# STM3205P_PowerSupply.net
KiCad netlist of a schematic drawn in Altium Designer
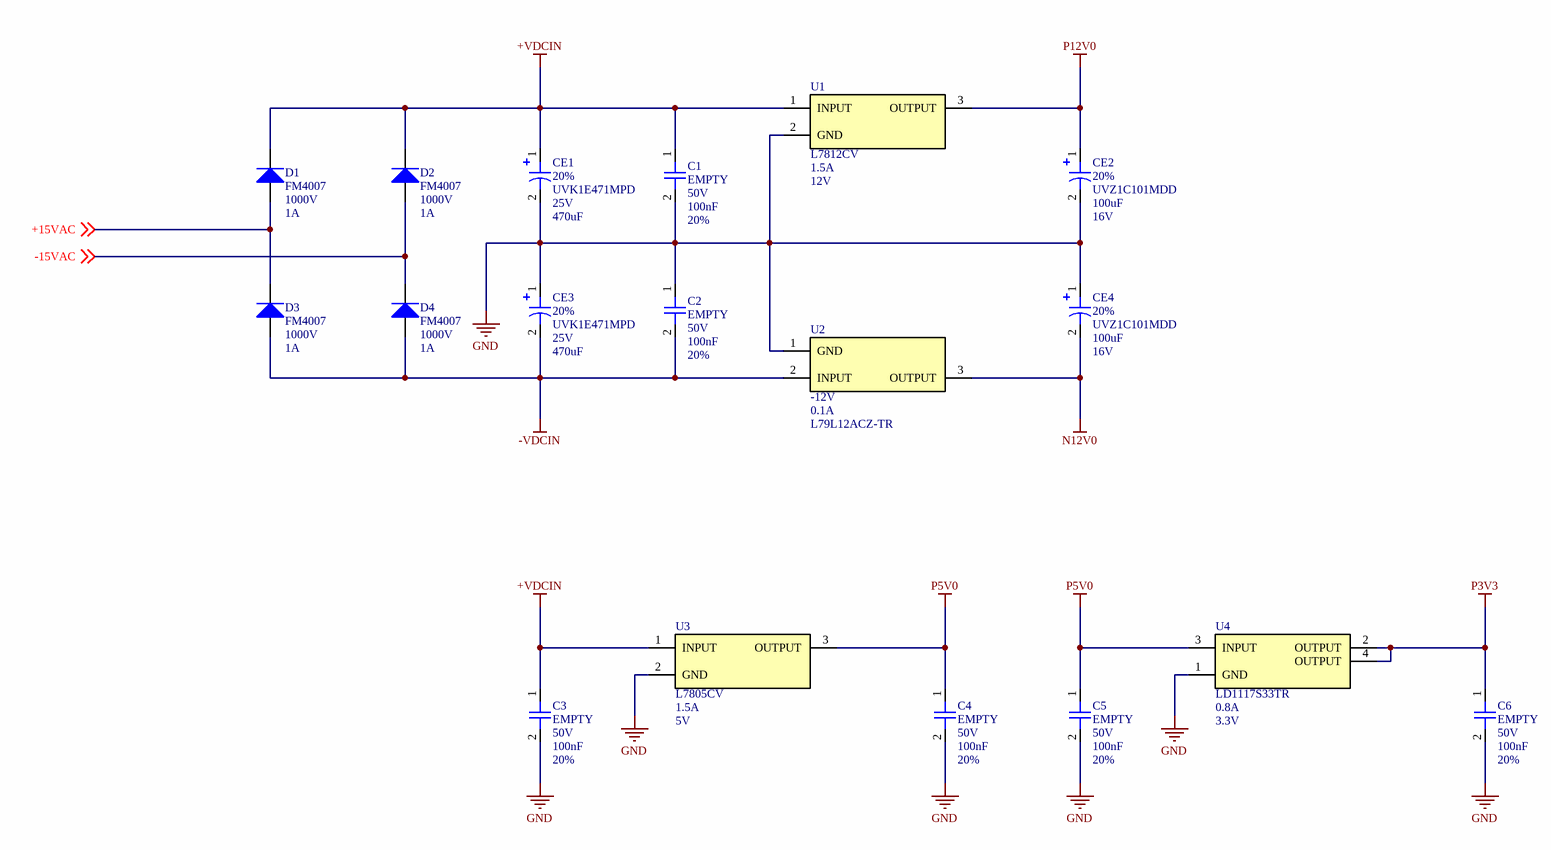
[diagram p0: STM3205P_PowerSupply.SchDoc]

(export (version "E")
  (design (tool "Eeschema 10.0.6"))
  (components
    (comp (ref "C1")
      (value "100nF")
      (footprint "CAP0603")
      (description "Surface Mount Multilayer Ceramic Chip Capacitors  for Commercial Applications")
      (fields
        (field (name "PARTNUMBER1") "EMPTY")
        (field (name "VOLTAGE") "50V")
        (field (name "TOLERANCE") "20%")
        (field (name "Comment") "CC0603")
        (field (name "PUBLISHER") "Lucas Moraes")
      )
      (libsource (lib "CeramicCapacitors") (part "CC0603"))
    )
    (comp (ref "C2")
      (value "100nF")
      (footprint "CAP0603")
      (description "Surface Mount Multilayer Ceramic Chip Capacitors  for Commercial Applications")
      (fields
        (field (name "PARTNUMBER1") "EMPTY")
        (field (name "VOLTAGE") "50V")
        (field (name "TOLERANCE") "20%")
        (field (name "Comment") "CC0603")
        (field (name "PUBLISHER") "Lucas Moraes")
      )
      (libsource (lib "CeramicCapacitors") (part "CC0603"))
    )
    (comp (ref "C3")
      (value "100nF")
      (footprint "CAP0603")
      (description "Surface Mount Multilayer Ceramic Chip Capacitors  for Commercial Applications")
      (fields
        (field (name "PARTNUMBER1") "EMPTY")
        (field (name "VOLTAGE") "50V")
        (field (name "TOLERANCE") "20%")
        (field (name "Comment") "CC0603")
        (field (name "PUBLISHER") "Lucas Moraes")
      )
      (libsource (lib "CeramicCapacitors") (part "CC0603"))
    )
    (comp (ref "C4")
      (value "100nF")
      (footprint "CAP0603")
      (description "Surface Mount Multilayer Ceramic Chip Capacitors  for Commercial Applications")
      (fields
        (field (name "PARTNUMBER1") "EMPTY")
        (field (name "VOLTAGE") "50V")
        (field (name "TOLERANCE") "20%")
        (field (name "Comment") "CC0603")
        (field (name "PUBLISHER") "Lucas Moraes")
      )
      (libsource (lib "CeramicCapacitors") (part "CC0603"))
    )
    (comp (ref "C5")
      (value "100nF")
      (footprint "CAP0603")
      (description "Surface Mount Multilayer Ceramic Chip Capacitors  for Commercial Applications")
      (fields
        (field (name "PARTNUMBER1") "EMPTY")
        (field (name "VOLTAGE") "50V")
        (field (name "TOLERANCE") "20%")
        (field (name "Comment") "CC0603")
        (field (name "PUBLISHER") "Lucas Moraes")
      )
      (libsource (lib "CeramicCapacitors") (part "CC0603"))
    )
    (comp (ref "C6")
      (value "100nF")
      (footprint "CAP0603")
      (description "Surface Mount Multilayer Ceramic Chip Capacitors  for Commercial Applications")
      (fields
        (field (name "PARTNUMBER1") "EMPTY")
        (field (name "VOLTAGE") "50V")
        (field (name "TOLERANCE") "20%")
        (field (name "Comment") "CC0603")
        (field (name "PUBLISHER") "Lucas Moraes")
      )
      (libsource (lib "CeramicCapacitors") (part "CC0603"))
    )
    (comp (ref "CE1")
      (value "470uF")
      (footprint "5.0-10.0-12.5")
      (description "Electrolytic Capacitor PTH")
      (fields
        (field (name "TOLERANCE") "20%")
        (field (name "PARTNUMBER1") "UVK1E471MPD")
        (field (name "VOLTAGE") "25V")
        (field (name "Comment") "25V 470uF")
        (field (name "PUBLISHER") "Lucas Moraes")
      )
      (libsource (lib "AluminumElectrolyticCapacitorsUVKNichicon") (part "25V 470uF"))
    )
    (comp (ref "CE2")
      (value "100uF")
      (footprint "2.0-5.0-11.0")
      (description "Electrolytic Capacitor PTH")
      (fields
        (field (name "TOLERANCE") "20%")
        (field (name "PARTNUMBER1") "UVZ1C101MDD")
        (field (name "VOLTAGE") "16V")
        (field (name "Comment") "16V 100uF")
        (field (name "PUBLISHER") "Lucas Moraes")
      )
      (libsource (lib "AluminumElectrolyticCapacitorsUVZNichicon") (part "16V 100uF"))
    )
    (comp (ref "CE3")
      (value "470uF")
      (footprint "5.0-10.0-12.5")
      (description "Electrolytic Capacitor PTH")
      (fields
        (field (name "TOLERANCE") "20%")
        (field (name "PARTNUMBER1") "UVK1E471MPD")
        (field (name "VOLTAGE") "25V")
        (field (name "Comment") "25V 470uF")
        (field (name "PUBLISHER") "Lucas Moraes")
      )
      (libsource (lib "AluminumElectrolyticCapacitorsUVKNichicon") (part "25V 470uF"))
    )
    (comp (ref "CE4")
      (value "100uF")
      (footprint "2.0-5.0-11.0")
      (description "Electrolytic Capacitor PTH")
      (fields
        (field (name "TOLERANCE") "20%")
        (field (name "PARTNUMBER1") "UVZ1C101MDD")
        (field (name "VOLTAGE") "16V")
        (field (name "Comment") "16V 100uF")
        (field (name "PUBLISHER") "Lucas Moraes")
      )
      (libsource (lib "AluminumElectrolyticCapacitorsUVZNichicon") (part "16V 100uF"))
    )
    (comp (ref "D1")
      (value "FM4007")
      (footprint "DO-214AC")
      (description "General Purpose Plastic Rectifier")
      (fields
        (field (name "PARTNUMBER1") "FM4007")
        (field (name "VRRM") "1000V")
        (field (name "IF") "1A")
        (field (name "PUBLISHER") "Lucas Moraes")
      )
      (libsource (lib "RectifierDiode") (part "FM4007"))
    )
    (comp (ref "D2")
      (value "FM4007")
      (footprint "DO-214AC")
      (description "General Purpose Plastic Rectifier")
      (fields
        (field (name "PARTNUMBER1") "FM4007")
        (field (name "VRRM") "1000V")
        (field (name "IF") "1A")
        (field (name "PUBLISHER") "Lucas Moraes")
      )
      (libsource (lib "RectifierDiode") (part "FM4007"))
    )
    (comp (ref "D3")
      (value "FM4007")
      (footprint "DO-214AC")
      (description "General Purpose Plastic Rectifier")
      (fields
        (field (name "PARTNUMBER1") "FM4007")
        (field (name "VRRM") "1000V")
        (field (name "IF") "1A")
        (field (name "PUBLISHER") "Lucas Moraes")
      )
      (libsource (lib "RectifierDiode") (part "FM4007"))
    )
    (comp (ref "D4")
      (value "FM4007")
      (footprint "DO-214AC")
      (description "General Purpose Plastic Rectifier")
      (fields
        (field (name "PARTNUMBER1") "FM4007")
        (field (name "VRRM") "1000V")
        (field (name "IF") "1A")
        (field (name "PUBLISHER") "Lucas Moraes")
      )
      (libsource (lib "RectifierDiode") (part "FM4007"))
    )
    (comp (ref "U1")
      (value "L7812CV")
      (footprint "TO-220A")
      (description "Positive voltage regulator ICs")
      (fields
        (field (name "PARTNUMBER1") "L7812CV")
        (field (name "CURRENT") "1.5A")
        (field (name "VOLTAGE") "12V")
        (field (name "PUBLISHER") "Lucas Moraes")
      )
      (libsource (lib "Voltage Regulators") (part "L7812CV"))
    )
    (comp (ref "U2")
      (value "L79L12ACZ-TR")
      (footprint "TO-92A_2.5")
      (description "Negative voltage regulator ICs")
      (fields
        (field (name "VOLTAGE") "-12V")
        (field (name "CURRENT") "0.1A")
        (field (name "PARTNUMBER1") "L79L12ACZ-TR")
        (field (name "PUBLISHER") "Lucas Moraes")
      )
      (libsource (lib "Voltage Regulators") (part "L79L12ACZ-TR"))
    )
    (comp (ref "U3")
      (value "L7805CV")
      (footprint "TO-220A")
      (description "Positive voltage regulator ICs")
      (fields
        (field (name "PARTNUMBER1") "L7805CV")
        (field (name "CURRENT") "1.5A")
        (field (name "VOLTAGE") "5V")
        (field (name "PUBLISHER") "Lucas Moraes")
      )
      (libsource (lib "Voltage Regulators") (part "L7805CV"))
    )
    (comp (ref "U4")
      (value "LD1117S33TR")
      (footprint "SOT-223")
      (description "Positive voltage regulator ICs")
      (fields
        (field (name "PARTNUMBER1") "LD1117S33TR")
        (field (name "CURRENT") "0.8A")
        (field (name "VOLTAGE") "3.3V")
        (field (name "PUBLISHER") "Lucas Moraes")
      )
      (libsource (lib "Voltage Regulators") (part "LD1117S33TR"))
    )
  )
  (nets
    (net (code "1") (name "+15VAC") (class "Default")
      (node (ref "D1") (pin "A") (pinfunction "A_A") (pintype "passive"))
      (node (ref "D3") (pin "K") (pinfunction "K_K") (pintype "passive"))
    )
    (net (code "2") (name "+VDCIN") (class "Default")
      (node (ref "C1") (pin "1") (pinfunction "1_1") (pintype "passive"))
      (node (ref "C3") (pin "1") (pinfunction "1_1") (pintype "passive"))
      (node (ref "CE1") (pin "1") (pinfunction "1_1") (pintype "passive"))
      (node (ref "D1") (pin "K") (pinfunction "K_K") (pintype "passive"))
      (node (ref "D2") (pin "K") (pinfunction "K_K") (pintype "passive"))
      (node (ref "U1") (pin "1") (pinfunction "INPUT_1") (pintype "passive"))
      (node (ref "U3") (pin "1") (pinfunction "INPUT_1") (pintype "passive"))
    )
    (net (code "3") (name "-15VAC") (class "Default")
      (node (ref "D2") (pin "A") (pinfunction "A_A") (pintype "passive"))
      (node (ref "D4") (pin "K") (pinfunction "K_K") (pintype "passive"))
    )
    (net (code "4") (name "-VDCIN") (class "Default")
      (node (ref "C2") (pin "2") (pinfunction "2_2") (pintype "passive"))
      (node (ref "CE3") (pin "2") (pinfunction "2_2") (pintype "passive"))
      (node (ref "D3") (pin "A") (pinfunction "A_A") (pintype "passive"))
      (node (ref "D4") (pin "A") (pinfunction "A_A") (pintype "passive"))
      (node (ref "U2") (pin "2") (pinfunction "INPUT_2") (pintype "passive"))
    )
    (net (code "5") (name "GND") (class "Default")
      (node (ref "C1") (pin "2") (pinfunction "2_2") (pintype "passive"))
      (node (ref "C2") (pin "1") (pinfunction "1_1") (pintype "passive"))
      (node (ref "C3") (pin "2") (pinfunction "2_2") (pintype "passive"))
      (node (ref "C4") (pin "2") (pinfunction "2_2") (pintype "passive"))
      (node (ref "C5") (pin "2") (pinfunction "2_2") (pintype "passive"))
      (node (ref "C6") (pin "2") (pinfunction "2_2") (pintype "passive"))
      (node (ref "CE1") (pin "2") (pinfunction "2_2") (pintype "passive"))
      (node (ref "CE2") (pin "2") (pinfunction "2_2") (pintype "passive"))
      (node (ref "CE3") (pin "1") (pinfunction "1_1") (pintype "passive"))
      (node (ref "CE4") (pin "1") (pinfunction "1_1") (pintype "passive"))
      (node (ref "U1") (pin "2") (pinfunction "GND_2") (pintype "passive"))
      (node (ref "U2") (pin "1") (pinfunction "GND_1") (pintype "passive"))
      (node (ref "U3") (pin "2") (pinfunction "GND_2") (pintype "passive"))
      (node (ref "U4") (pin "1") (pinfunction "GND_1") (pintype "passive"))
    )
    (net (code "6") (name "N12V0") (class "Default")
      (node (ref "CE4") (pin "2") (pinfunction "2_2") (pintype "passive"))
      (node (ref "U2") (pin "3") (pinfunction "OUTPUT_3") (pintype "passive"))
    )
    (net (code "7") (name "P3V3") (class "Default")
      (node (ref "C6") (pin "1") (pinfunction "1_1") (pintype "passive"))
      (node (ref "U4") (pin "2") (pinfunction "OUTPUT_2") (pintype "passive"))
      (node (ref "U4") (pin "4") (pinfunction "OUTPUT_4") (pintype "passive"))
    )
    (net (code "8") (name "P5V0") (class "Default")
      (node (ref "C4") (pin "1") (pinfunction "1_1") (pintype "passive"))
      (node (ref "C5") (pin "1") (pinfunction "1_1") (pintype "passive"))
      (node (ref "U3") (pin "3") (pinfunction "OUTPUT_3") (pintype "passive"))
      (node (ref "U4") (pin "3") (pinfunction "INPUT_3") (pintype "passive"))
    )
    (net (code "9") (name "P12V0") (class "Default")
      (node (ref "CE2") (pin "1") (pinfunction "1_1") (pintype "passive"))
      (node (ref "U1") (pin "3") (pinfunction "OUTPUT_3") (pintype "passive"))
    )
  )
)
